# Magnetometer_Filter.net
KiCad netlist of a schematic drawn in Altium Designer
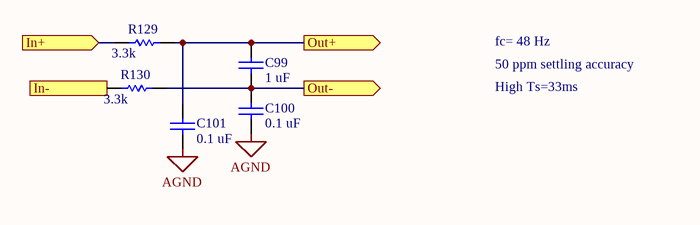
[diagram p0: Magnetometer_Filter.SchDoc]

(export (version "E")
  (design (tool "Eeschema 10.0.6"))
  (components
    (comp (ref "C99")
      (value "1 uF")
      (footprint "CAPC1005X60X30NL05T10")
      (fields (field (name "PART NUMBER") "C0402C105M8PACTU") (field (name "MANUFACTURER") "Kemet"))
      (libsource (lib "Altium Content Vault") (part "CAP"))
    )
    (comp (ref "C100")
      (value "0.1 uF")
      (footprint "CAPC0402(1005)60_L")
      (description "CAP 100nF 16V ±5% 0402 (1005 Metric) Thickness 0.6mm SMD")
      (fields (field (name "TOLERANCE") "Â±5%"))
      (libsource (lib "Altium Content Vault") (part "CAP"))
    )
    (comp (ref "C101")
      (value "0.1 uF")
      (footprint "CAPC0402(1005)60_L")
      (description "CAP 100nF 16V ±5% 0402 (1005 Metric) Thickness 0.6mm SMD")
      (fields (field (name "TOLERANCE") "Â±5%"))
      (libsource (lib "Altium Content Vault") (part "CAP"))
    )
    (comp (ref "R129")
      (value "CRCW04023K30JNED")
      (footprint "RESC1005X40X25LL05T05")
      (fields (field (name "MANUFACTURER") "Vishay Dale") (field (name "RESISTANCE") "3.3k"))
      (libsource (lib "Altium Content Vault") (part "RES"))
    )
    (comp (ref "R130")
      (value "CRCW04023K30JNED")
      (footprint "RESC1005X40X25LL05T05")
      (fields (field (name "MANUFACTURER") "Vishay Dale") (field (name "RESISTANCE") "3.3k"))
      (libsource (lib "Altium Content Vault") (part "RES"))
    )
  )
  (nets
    (net (code "1") (name "/In+") (class "Default")
      (node (ref "R129") (pin "1") (pinfunction "1_1") (pintype "passive"))
    )
    (net (code "2") (name "/In-") (class "Default")
      (node (ref "R130") (pin "1") (pinfunction "1_1") (pintype "passive"))
    )
    (net (code "3") (name "/Out+") (class "Default")
      (node (ref "C101") (pin "2") (pinfunction "2_2") (pintype "passive"))
      (node (ref "C99") (pin "2") (pinfunction "2_2") (pintype "passive"))
      (node (ref "R129") (pin "2") (pinfunction "2_2") (pintype "passive"))
    )
    (net (code "4") (name "/Out-") (class "Default")
      (node (ref "C100") (pin "2") (pinfunction "2_2") (pintype "passive"))
      (node (ref "C99") (pin "1") (pinfunction "1_1") (pintype "passive"))
      (node (ref "R130") (pin "2") (pinfunction "2_2") (pintype "passive"))
    )
    (net (code "5") (name "AGND") (class "Default")
      (node (ref "C100") (pin "1") (pinfunction "1_1") (pintype "passive"))
      (node (ref "C101") (pin "1") (pinfunction "1_1") (pintype "passive"))
    )
  )
)
